# LPC1114_Bare_Metal_v01.net
KiCad netlist of a schematic drawn in EAGLE
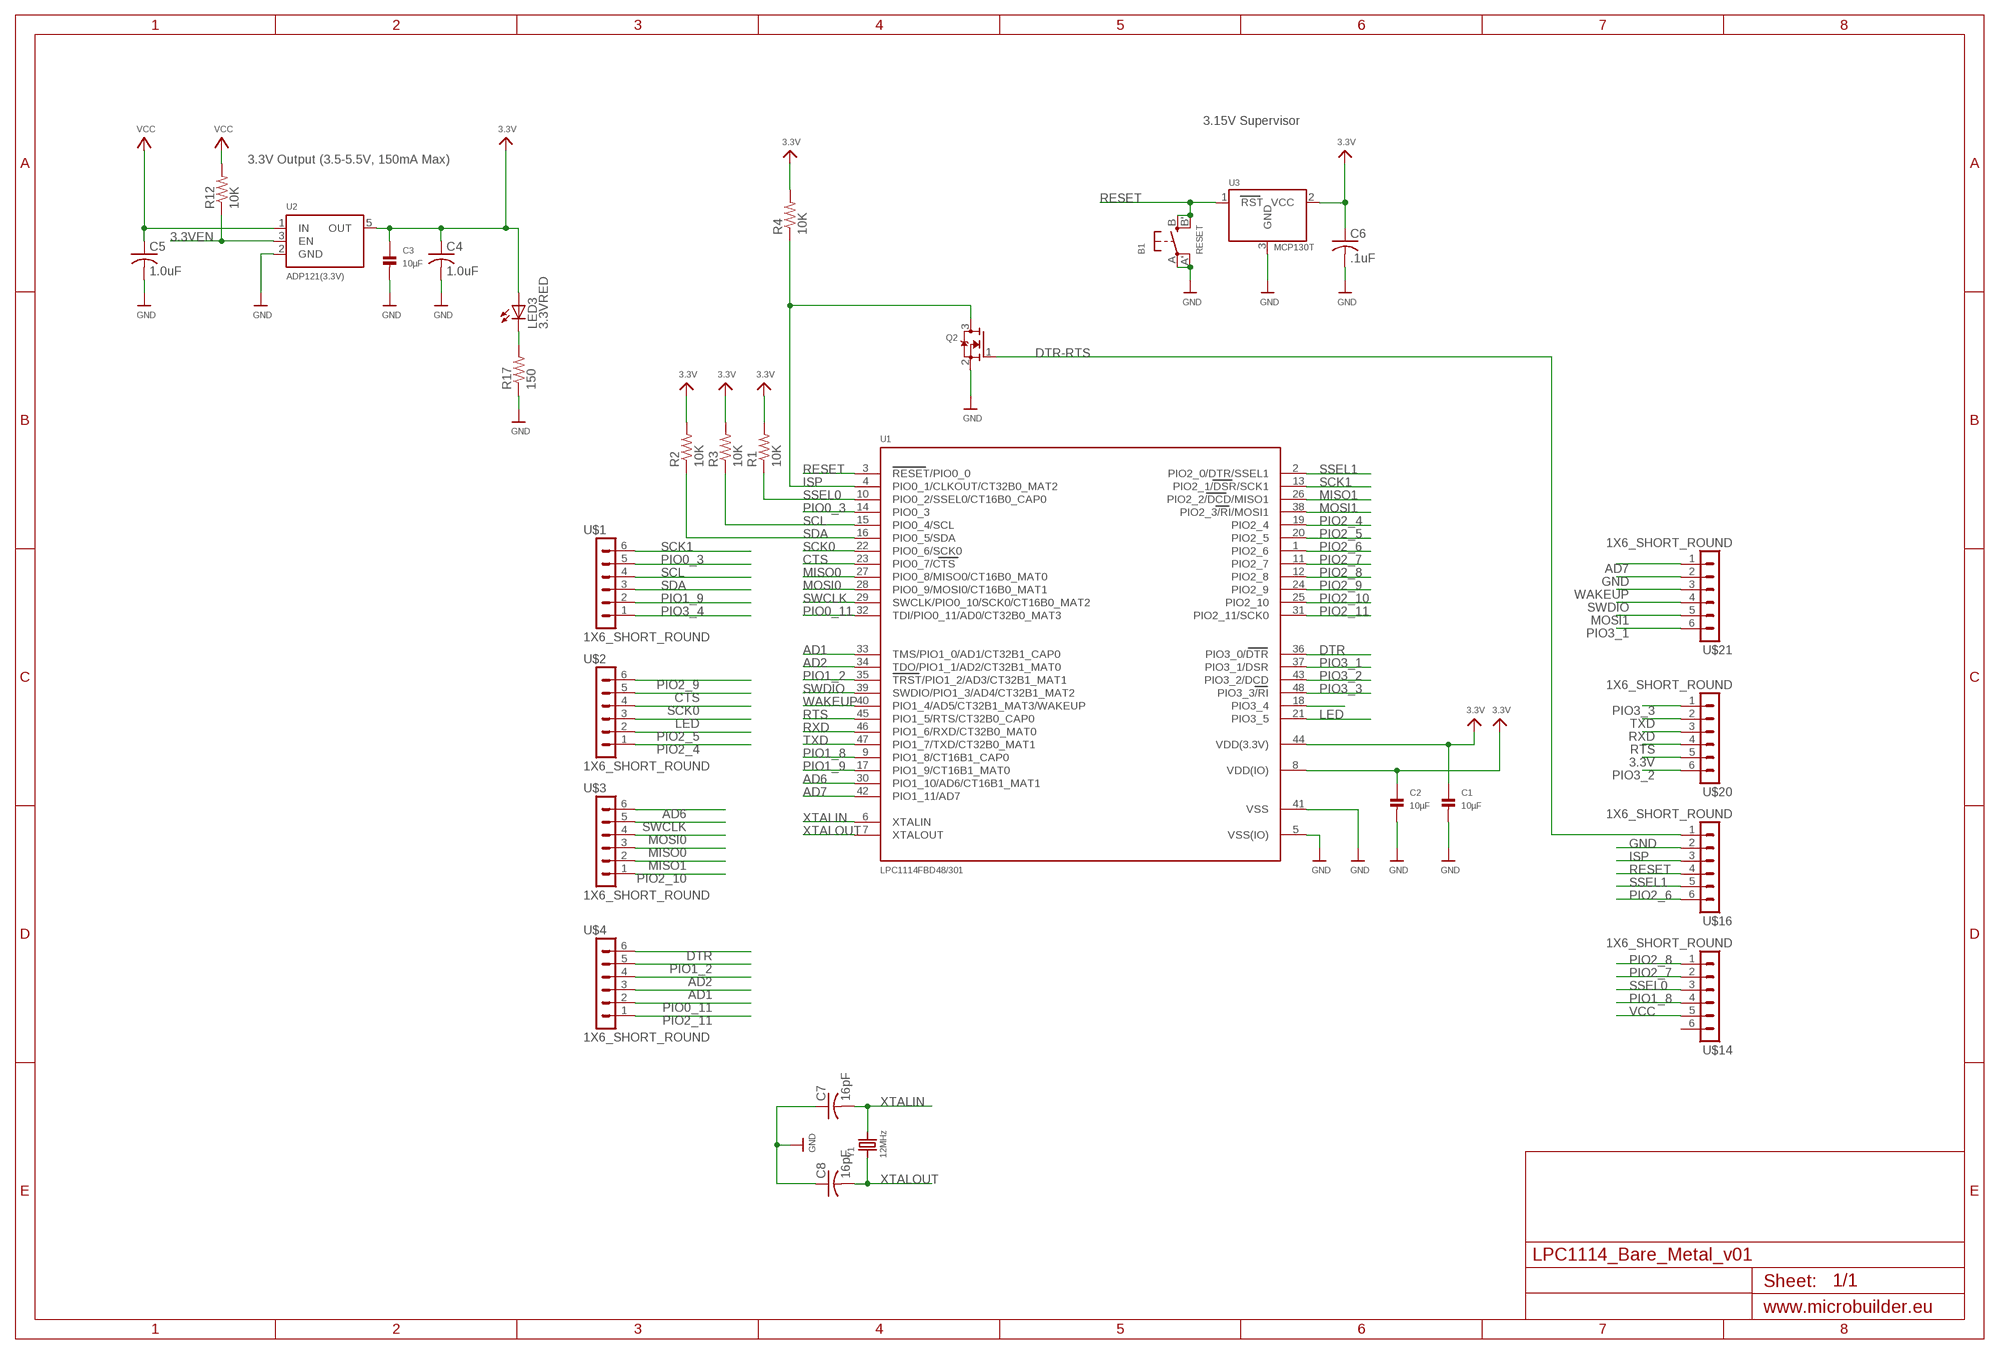
[diagram p0: schematic, sheet 1]

(export (version "E")
  (design (tool "Eeschema 10.0.6"))
  (components
    (comp (ref "B1")
      (value "RESET")
      (footprint "eagle-import:EVQ-Q2")
      (libsource (lib "eagle-import") (part "BUTTON_SMT"))
    )
    (comp (ref "C1")
      (value "10µF")
      (footprint "eagle-import:0805")
      (libsource (lib "eagle-import") (part "CAP_CERAMIC0805"))
    )
    (comp (ref "C2")
      (value "10µF")
      (footprint "eagle-import:0805")
      (libsource (lib "eagle-import") (part "CAP_CERAMIC0805"))
    )
    (comp (ref "C3")
      (value "10µF")
      (footprint "eagle-import:0805")
      (libsource (lib "eagle-import") (part "CAP_CERAMIC0805"))
    )
    (comp (ref "C4")
      (value "1.0uF")
      (footprint "eagle-import:C0402K")
      (libsource (lib "eagle-import") (part "C-USC0402K"))
    )
    (comp (ref "C5")
      (value "1.0uF")
      (footprint "eagle-import:C0402K")
      (libsource (lib "eagle-import") (part "C-USC0402K"))
    )
    (comp (ref "C6")
      (value ".1uF")
      (footprint "eagle-import:C0402K")
      (libsource (lib "eagle-import") (part "C-USC0402K"))
    )
    (comp (ref "C7")
      (value "16pF")
      (footprint "eagle-import:C0402K")
      (libsource (lib "eagle-import") (part "C-USC0402K"))
    )
    (comp (ref "C8")
      (value "16pF")
      (footprint "eagle-import:C0402K")
      (libsource (lib "eagle-import") (part "C-USC0402K"))
    )
    (comp (ref "LED3")
      (value "3.3VRED")
      (footprint "eagle-import:SML0603")
      (libsource (lib "eagle-import") (part "LEDSML0603"))
    )
    (comp (ref "Q2")
      (value "MOSFET-NREFLOW")
      (footprint "eagle-import:SOT23")
      (libsource (lib "eagle-import") (part "MOSFET-NREFLOW"))
    )
    (comp (ref "R1")
      (value "10K")
      (footprint "eagle-import:R0402")
      (libsource (lib "eagle-import") (part "R-US_R0402"))
    )
    (comp (ref "R2")
      (value "10K")
      (footprint "eagle-import:R0402")
      (libsource (lib "eagle-import") (part "R-US_R0402"))
    )
    (comp (ref "R3")
      (value "10K")
      (footprint "eagle-import:R0402")
      (libsource (lib "eagle-import") (part "R-US_R0402"))
    )
    (comp (ref "R4")
      (value "10K")
      (footprint "eagle-import:R0402")
      (libsource (lib "eagle-import") (part "R-US_R0402"))
    )
    (comp (ref "R12")
      (value "10K")
      (footprint "eagle-import:R0402")
      (libsource (lib "eagle-import") (part "R-US_R0402"))
    )
    (comp (ref "R17")
      (value "150")
      (footprint "eagle-import:R0402")
      (libsource (lib "eagle-import") (part "R-US_R0402"))
    )
    (comp (ref "U$1")
      (value "1X6_SHORT_ROUND")
      (footprint "eagle-import:1X6_SHORT_ROUND")
      (libsource (lib "eagle-import") (part "1X6_SHORT_ROUND"))
    )
    (comp (ref "U$2")
      (value "1X6_SHORT_ROUND")
      (footprint "eagle-import:1X6_SHORT_ROUND")
      (libsource (lib "eagle-import") (part "1X6_SHORT_ROUND"))
    )
    (comp (ref "U$3")
      (value "1X6_SHORT_ROUND")
      (footprint "eagle-import:1X6_SHORT_ROUND")
      (libsource (lib "eagle-import") (part "1X6_SHORT_ROUND"))
    )
    (comp (ref "U$4")
      (value "1X6_SHORT_ROUND")
      (footprint "eagle-import:1X6_SHORT_ROUND")
      (libsource (lib "eagle-import") (part "1X6_SHORT_ROUND"))
    )
    (comp (ref "U$14")
      (value "1X6_SHORT_ROUND")
      (footprint "eagle-import:1X6_SHORT_ROUND")
      (libsource (lib "eagle-import") (part "1X6_SHORT_ROUND"))
    )
    (comp (ref "U$16")
      (value "1X6_SHORT_ROUND")
      (footprint "eagle-import:1X6_SHORT_ROUND")
      (libsource (lib "eagle-import") (part "1X6_SHORT_ROUND"))
    )
    (comp (ref "U$20")
      (value "1X6_SHORT_ROUND")
      (footprint "eagle-import:1X6_SHORT_ROUND")
      (libsource (lib "eagle-import") (part "1X6_SHORT_ROUND"))
    )
    (comp (ref "U$21")
      (value "1X6_SHORT_ROUND")
      (footprint "eagle-import:1X6_SHORT_ROUND")
      (libsource (lib "eagle-import") (part "1X6_SHORT_ROUND"))
    )
    (comp (ref "U1")
      (value "LPC1114FBD48/301")
      (footprint "eagle-import:LQFP48")
      (libsource (lib "eagle-import") (part "LPC1113/4"))
    )
    (comp (ref "U2")
      (value "ADP121(3.3V)")
      (footprint "eagle-import:SOT23-5")
      (libsource (lib "eagle-import") (part "ADP121"))
    )
    (comp (ref "U3")
      (value "MCP130T")
      (footprint "eagle-import:SOT23-R")
      (libsource (lib "eagle-import") (part "MCP130TREFLOW"))
    )
    (comp (ref "Y1")
      (value "12MHz")
      (footprint "eagle-import:CRYSTAL_3.2X2.5")
      (libsource (lib "eagle-import") (part "CRYSTALTHIN"))
    )
  )
  (nets
    (net (code "1") (name "/3.3VEN") (class "Default")
      (node (ref "R12") (pin "1") (pinfunction "1_1") (pintype "passive"))
      (node (ref "U2") (pin "3") (pinfunction "EN_3") (pintype "bidirectional"))
    )
    (net (code "2") (name "/AD1") (class "Default")
      (node (ref "U$4") (pin "3") (pinfunction "3_3") (pintype "passive"))
      (node (ref "U1") (pin "33") (pinfunction "TMS/PIO1_0/AD1/CT32B1_CAP0_33") (pintype "bidirectional"))
    )
    (net (code "3") (name "/AD2") (class "Default")
      (node (ref "U$4") (pin "4") (pinfunction "4_4") (pintype "passive"))
      (node (ref "U1") (pin "34") (pinfunction "TDO/PIO1_1/AD2/CT32B1_MAT0_34") (pintype "bidirectional"))
    )
    (net (code "4") (name "/AD6") (class "Default")
      (node (ref "U$3") (pin "6") (pinfunction "6_6") (pintype "passive"))
      (node (ref "U1") (pin "30") (pinfunction "PIO1_10/AD6/CT16B1_MAT1_30") (pintype "bidirectional"))
    )
    (net (code "5") (name "/AD7") (class "Default")
      (node (ref "U$21") (pin "1") (pinfunction "1_1") (pintype "passive"))
      (node (ref "U1") (pin "42") (pinfunction "PIO1_11/AD7_42") (pintype "bidirectional"))
    )
    (net (code "6") (name "/CTS") (class "Default")
      (node (ref "U$2") (pin "5") (pinfunction "5_5") (pintype "passive"))
      (node (ref "U1") (pin "23") (pinfunction "PIO0_7/CTS_23") (pintype "bidirectional"))
    )
    (net (code "7") (name "/DTR") (class "Default")
      (node (ref "U$4") (pin "6") (pinfunction "6_6") (pintype "passive"))
      (node (ref "U1") (pin "36") (pinfunction "PIO3_0/DTR_36") (pintype "bidirectional"))
    )
    (net (code "8") (name "/DTR-RTS") (class "Default")
      (node (ref "Q2") (pin "1") (pinfunction "G_1") (pintype "bidirectional"))
      (node (ref "U$16") (pin "1") (pinfunction "1_1") (pintype "passive"))
    )
    (net (code "9") (name "/ISP") (class "Default")
      (node (ref "Q2") (pin "3") (pinfunction "D_3") (pintype "bidirectional"))
      (node (ref "R4") (pin "1") (pinfunction "1_1") (pintype "passive"))
      (node (ref "U$16") (pin "3") (pinfunction "3_3") (pintype "passive"))
      (node (ref "U1") (pin "4") (pinfunction "PIO0_1/CLKOUT/CT32B0_MAT2_4") (pintype "bidirectional"))
    )
    (net (code "10") (name "/LED") (class "Default")
      (node (ref "U$2") (pin "3") (pinfunction "3_3") (pintype "passive"))
      (node (ref "U1") (pin "21") (pinfunction "PIO3_5_21") (pintype "bidirectional"))
    )
    (net (code "11") (name "/MISO0") (class "Default")
      (node (ref "U$3") (pin "3") (pinfunction "3_3") (pintype "passive"))
      (node (ref "U1") (pin "27") (pinfunction "PIO0_8/MISO0/CT16B0_MAT0_27") (pintype "bidirectional"))
    )
    (net (code "12") (name "/MISO1") (class "Default")
      (node (ref "U$3") (pin "2") (pinfunction "2_2") (pintype "passive"))
      (node (ref "U1") (pin "26") (pinfunction "PIO2_2/DCD/MISO1_26") (pintype "bidirectional"))
    )
    (net (code "13") (name "/MOSI0") (class "Default")
      (node (ref "U$3") (pin "4") (pinfunction "4_4") (pintype "passive"))
      (node (ref "U1") (pin "28") (pinfunction "PIO0_9/MOSI0/CT16B0_MAT1_28") (pintype "bidirectional"))
    )
    (net (code "14") (name "/MOSI1") (class "Default")
      (node (ref "U$21") (pin "5") (pinfunction "5_5") (pintype "passive"))
      (node (ref "U1") (pin "38") (pinfunction "PIO2_3/RI/MOSI1_38") (pintype "bidirectional"))
    )
    (net (code "15") (name "/PIO0_3") (class "Default")
      (node (ref "U$1") (pin "5") (pinfunction "5_5") (pintype "passive"))
      (node (ref "U1") (pin "14") (pinfunction "PIO0_3_14") (pintype "bidirectional"))
    )
    (net (code "16") (name "/PIO0_11") (class "Default")
      (node (ref "U$4") (pin "2") (pinfunction "2_2") (pintype "passive"))
      (node (ref "U1") (pin "32") (pinfunction "TDI/PIO0_11/AD0/CT32B0_MAT3_32") (pintype "bidirectional"))
    )
    (net (code "17") (name "/PIO1_2") (class "Default")
      (node (ref "U$4") (pin "5") (pinfunction "5_5") (pintype "passive"))
      (node (ref "U1") (pin "35") (pinfunction "TRST/PIO1_2/AD3/CT32B1_MAT1_35") (pintype "bidirectional"))
    )
    (net (code "18") (name "/PIO1_8") (class "Default")
      (node (ref "U$14") (pin "4") (pinfunction "4_4") (pintype "passive"))
      (node (ref "U1") (pin "9") (pinfunction "PIO1_8/CT16B1_CAP0_9") (pintype "bidirectional"))
    )
    (net (code "19") (name "/PIO1_9") (class "Default")
      (node (ref "U$1") (pin "2") (pinfunction "2_2") (pintype "passive"))
      (node (ref "U1") (pin "17") (pinfunction "PIO1_9/CT16B1_MAT0_17") (pintype "bidirectional"))
    )
    (net (code "20") (name "/PIO2_4") (class "Default")
      (node (ref "U$2") (pin "1") (pinfunction "1_1") (pintype "passive"))
      (node (ref "U1") (pin "19") (pinfunction "PIO2_4_19") (pintype "bidirectional"))
    )
    (net (code "21") (name "/PIO2_5") (class "Default")
      (node (ref "U$2") (pin "2") (pinfunction "2_2") (pintype "passive"))
      (node (ref "U1") (pin "20") (pinfunction "PIO2_5_20") (pintype "bidirectional"))
    )
    (net (code "22") (name "/PIO2_6") (class "Default")
      (node (ref "U$16") (pin "6") (pinfunction "6_6") (pintype "passive"))
      (node (ref "U1") (pin "1") (pinfunction "PIO2_6_1") (pintype "bidirectional"))
    )
    (net (code "23") (name "/PIO2_7") (class "Default")
      (node (ref "U$14") (pin "2") (pinfunction "2_2") (pintype "passive"))
      (node (ref "U1") (pin "11") (pinfunction "PIO2_7_11") (pintype "bidirectional"))
    )
    (net (code "24") (name "/PIO2_8") (class "Default")
      (node (ref "U$14") (pin "1") (pinfunction "1_1") (pintype "passive"))
      (node (ref "U1") (pin "12") (pinfunction "PIO2_8_12") (pintype "bidirectional"))
    )
    (net (code "25") (name "/PIO2_9") (class "Default")
      (node (ref "U$2") (pin "6") (pinfunction "6_6") (pintype "passive"))
      (node (ref "U1") (pin "24") (pinfunction "PIO2_9_24") (pintype "bidirectional"))
    )
    (net (code "26") (name "/PIO2_10") (class "Default")
      (node (ref "U$3") (pin "1") (pinfunction "1_1") (pintype "passive"))
      (node (ref "U1") (pin "25") (pinfunction "PIO2_10_25") (pintype "bidirectional"))
    )
    (net (code "27") (name "/PIO2_11") (class "Default")
      (node (ref "U$4") (pin "1") (pinfunction "1_1") (pintype "passive"))
      (node (ref "U1") (pin "31") (pinfunction "PIO2_11/SCK0_31") (pintype "bidirectional"))
    )
    (net (code "28") (name "/PIO3_1") (class "Default")
      (node (ref "U$21") (pin "6") (pinfunction "6_6") (pintype "passive"))
      (node (ref "U1") (pin "37") (pinfunction "PIO3_1/DSR_37") (pintype "bidirectional"))
    )
    (net (code "29") (name "/PIO3_2") (class "Default")
      (node (ref "U$20") (pin "6") (pinfunction "6_6") (pintype "passive"))
      (node (ref "U1") (pin "43") (pinfunction "PIO3_2/DCD_43") (pintype "bidirectional"))
    )
    (net (code "30") (name "/PIO3_3") (class "Default")
      (node (ref "U$20") (pin "1") (pinfunction "1_1") (pintype "passive"))
      (node (ref "U1") (pin "48") (pinfunction "PIO3_3/RI_48") (pintype "bidirectional"))
    )
    (net (code "31") (name "/PIO3_4") (class "Default")
      (node (ref "U$1") (pin "1") (pinfunction "1_1") (pintype "passive"))
      (node (ref "U1") (pin "18") (pinfunction "PIO3_4_18") (pintype "bidirectional"))
    )
    (net (code "32") (name "/RESET") (class "Default")
      (node (ref "B1") (pin "B") (pinfunction "S_B") (pintype "passive"))
      (node (ref "B1") (pin "B'") (pinfunction "S1_B'") (pintype "passive"))
      (node (ref "U$16") (pin "4") (pinfunction "4_4") (pintype "passive"))
      (node (ref "U1") (pin "3") (pinfunction "RESET/PIO0_0_3") (pintype "bidirectional"))
      (node (ref "U3") (pin "1") (pinfunction "RST_1") (pintype "bidirectional"))
    )
    (net (code "33") (name "/RTS") (class "Default")
      (node (ref "U$20") (pin "4") (pinfunction "4_4") (pintype "passive"))
      (node (ref "U1") (pin "45") (pinfunction "PIO1_5/RTS/CT32B0_CAP0_45") (pintype "bidirectional"))
    )
    (net (code "34") (name "/RXD") (class "Default")
      (node (ref "U$20") (pin "3") (pinfunction "3_3") (pintype "passive"))
      (node (ref "U1") (pin "46") (pinfunction "PIO1_6/RXD/CT32B0_MAT0_46") (pintype "bidirectional"))
    )
    (net (code "35") (name "/SCK0") (class "Default")
      (node (ref "U$2") (pin "4") (pinfunction "4_4") (pintype "passive"))
      (node (ref "U1") (pin "22") (pinfunction "PIO0_6/SCK0_22") (pintype "bidirectional"))
    )
    (net (code "36") (name "/SCK1") (class "Default")
      (node (ref "U$1") (pin "6") (pinfunction "6_6") (pintype "passive"))
      (node (ref "U1") (pin "13") (pinfunction "PIO2_1/DSR/SCK1_13") (pintype "bidirectional"))
    )
    (net (code "37") (name "/SCL") (class "Default")
      (node (ref "R3") (pin "1") (pinfunction "1_1") (pintype "passive"))
      (node (ref "U$1") (pin "4") (pinfunction "4_4") (pintype "passive"))
      (node (ref "U1") (pin "15") (pinfunction "PIO0_4/SCL_15") (pintype "bidirectional"))
    )
    (net (code "38") (name "/SDA") (class "Default")
      (node (ref "R2") (pin "1") (pinfunction "1_1") (pintype "passive"))
      (node (ref "U$1") (pin "3") (pinfunction "3_3") (pintype "passive"))
      (node (ref "U1") (pin "16") (pinfunction "PIO0_5/SDA_16") (pintype "bidirectional"))
    )
    (net (code "39") (name "/SSEL0") (class "Default")
      (node (ref "R1") (pin "1") (pinfunction "1_1") (pintype "passive"))
      (node (ref "U$14") (pin "3") (pinfunction "3_3") (pintype "passive"))
      (node (ref "U1") (pin "10") (pinfunction "PIO0_2/SSEL0/CT16B0_CAP0_10") (pintype "bidirectional"))
    )
    (net (code "40") (name "/SSEL1") (class "Default")
      (node (ref "U$16") (pin "5") (pinfunction "5_5") (pintype "passive"))
      (node (ref "U1") (pin "2") (pinfunction "PIO2_0/DTR/SSEL1_2") (pintype "bidirectional"))
    )
    (net (code "41") (name "/SWCLK") (class "Default")
      (node (ref "U$3") (pin "5") (pinfunction "5_5") (pintype "passive"))
      (node (ref "U1") (pin "29") (pinfunction "SWCLK/PIO0_10/SCK0/CT16B0_MAT2_29") (pintype "bidirectional"))
    )
    (net (code "42") (name "/SWDIO") (class "Default")
      (node (ref "U$21") (pin "4") (pinfunction "4_4") (pintype "passive"))
      (node (ref "U1") (pin "39") (pinfunction "SWDIO/PIO1_3/AD4/CT32B1_MAT2_39") (pintype "bidirectional"))
    )
    (net (code "43") (name "/TXD") (class "Default")
      (node (ref "U$20") (pin "2") (pinfunction "2_2") (pintype "passive"))
      (node (ref "U1") (pin "47") (pinfunction "PIO1_7/TXD/CT32B0_MAT1_47") (pintype "bidirectional"))
    )
    (net (code "44") (name "/WAKEUP") (class "Default")
      (node (ref "U$21") (pin "3") (pinfunction "3_3") (pintype "passive"))
      (node (ref "U1") (pin "40") (pinfunction "PIO1_4/AD5/CT32B1_MAT3/WAKEUP_40") (pintype "bidirectional"))
    )
    (net (code "45") (name "/XTALIN") (class "Default")
      (node (ref "C7") (pin "2") (pinfunction "2_2") (pintype "passive"))
      (node (ref "U1") (pin "6") (pinfunction "XTALIN_6") (pintype "input"))
      (node (ref "Y1") (pin "2") (pinfunction "2_2") (pintype "passive"))
    )
    (net (code "46") (name "/XTALOUT") (class "Default")
      (node (ref "C8") (pin "2") (pinfunction "2_2") (pintype "passive"))
      (node (ref "U1") (pin "7") (pinfunction "XTALOUT_7") (pintype "output"))
      (node (ref "Y1") (pin "1") (pinfunction "1_1") (pintype "passive"))
    )
    (net (code "47") (name "3.3V") (class "Default")
      (node (ref "C1") (pin "1") (pinfunction "P$1_1") (pintype "passive"))
      (node (ref "C2") (pin "1") (pinfunction "P$1_1") (pintype "passive"))
      (node (ref "C3") (pin "1") (pinfunction "P$1_1") (pintype "passive"))
      (node (ref "C4") (pin "1") (pinfunction "1_1") (pintype "passive"))
      (node (ref "C6") (pin "1") (pinfunction "1_1") (pintype "passive"))
      (node (ref "LED3") (pin "A") (pinfunction "A_A") (pintype "passive"))
      (node (ref "R1") (pin "2") (pinfunction "2_2") (pintype "passive"))
      (node (ref "R2") (pin "2") (pinfunction "2_2") (pintype "passive"))
      (node (ref "R3") (pin "2") (pinfunction "2_2") (pintype "passive"))
      (node (ref "R4") (pin "2") (pinfunction "2_2") (pintype "passive"))
      (node (ref "U$20") (pin "5") (pinfunction "5_5") (pintype "passive"))
      (node (ref "U1") (pin "44") (pinfunction "VDD(3.3V)_44") (pintype "power_in"))
      (node (ref "U1") (pin "8") (pinfunction "VDD(IO)_8") (pintype "power_in"))
      (node (ref "U2") (pin "5") (pinfunction "OUT_5") (pintype "bidirectional"))
      (node (ref "U3") (pin "2") (pinfunction "VCC_2") (pintype "power_in"))
    )
    (net (code "48") (name "GND") (class "Default")
      (node (ref "B1") (pin "A") (pinfunction "P_A") (pintype "passive"))
      (node (ref "B1") (pin "A'") (pinfunction "P1_A'") (pintype "passive"))
      (node (ref "C1") (pin "2") (pinfunction "P$2_2") (pintype "passive"))
      (node (ref "C2") (pin "2") (pinfunction "P$2_2") (pintype "passive"))
      (node (ref "C3") (pin "2") (pinfunction "P$2_2") (pintype "passive"))
      (node (ref "C4") (pin "2") (pinfunction "2_2") (pintype "passive"))
      (node (ref "C5") (pin "2") (pinfunction "2_2") (pintype "passive"))
      (node (ref "C6") (pin "2") (pinfunction "2_2") (pintype "passive"))
      (node (ref "C7") (pin "1") (pinfunction "1_1") (pintype "passive"))
      (node (ref "C8") (pin "1") (pinfunction "1_1") (pintype "passive"))
      (node (ref "Q2") (pin "2") (pinfunction "S_2") (pintype "bidirectional"))
      (node (ref "R17") (pin "1") (pinfunction "1_1") (pintype "passive"))
      (node (ref "U$16") (pin "2") (pinfunction "2_2") (pintype "passive"))
      (node (ref "U$21") (pin "2") (pinfunction "2_2") (pintype "passive"))
      (node (ref "U1") (pin "41") (pinfunction "VSS_41") (pintype "power_in"))
      (node (ref "U1") (pin "5") (pinfunction "VSS(IO)_5") (pintype "power_in"))
      (node (ref "U2") (pin "2") (pinfunction "GND_2") (pintype "bidirectional"))
      (node (ref "U3") (pin "3") (pinfunction "GND_3") (pintype "power_in"))
    )
    (net (code "49") (name "Net-(LED3-PadC)") (class "Default")
      (node (ref "LED3") (pin "C") (pinfunction "C_C") (pintype "passive"))
      (node (ref "R17") (pin "2") (pinfunction "2_2") (pintype "passive"))
    )
    (net (code "50") (name "VCC") (class "Default")
      (node (ref "C5") (pin "1") (pinfunction "1_1") (pintype "passive"))
      (node (ref "R12") (pin "2") (pinfunction "2_2") (pintype "passive"))
      (node (ref "U$14") (pin "5") (pinfunction "5_5") (pintype "passive"))
      (node (ref "U2") (pin "1") (pinfunction "IN_1") (pintype "bidirectional"))
    )
    (net (code "51") (name "unconnected-(U$14-Pad6)") (class "Default")
      (node (ref "U$14") (pin "6") (pinfunction "6_6") (pintype "passive"))
    )
  )
)
